# Battey_Voltage.net
KiCad netlist of a schematic drawn in Altium Designer
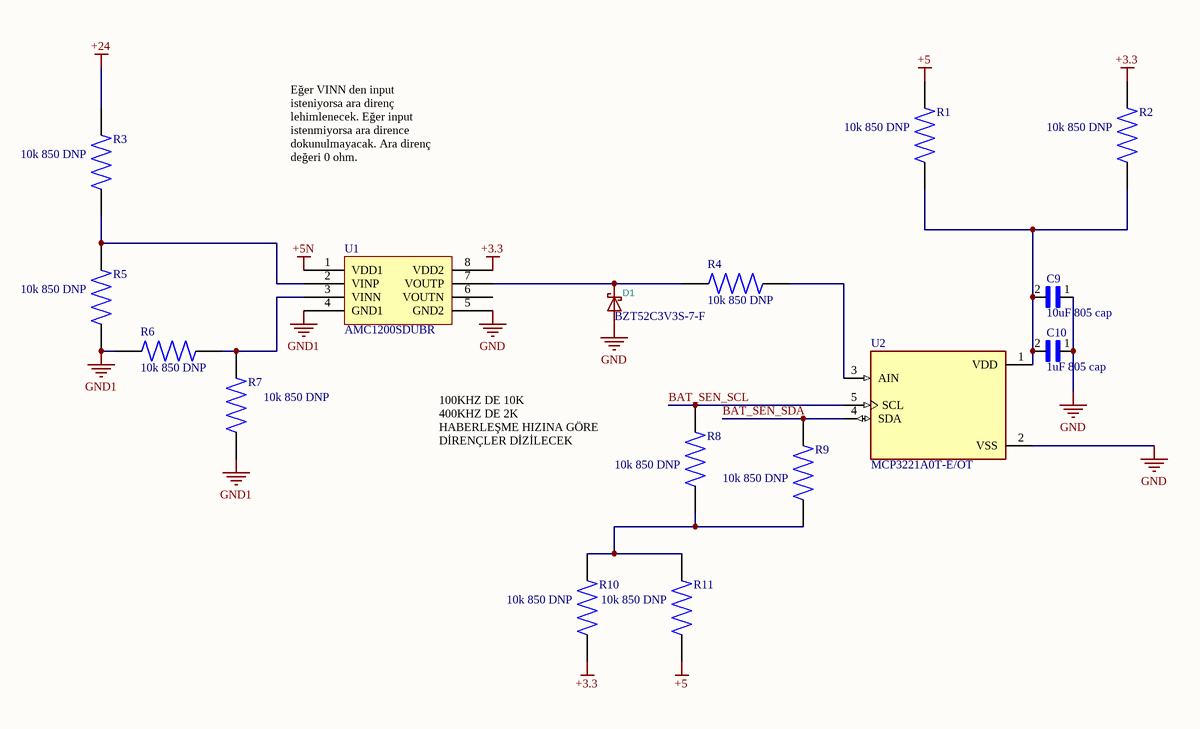
[diagram p0: Battey_Voltage.SchDoc]

(export (version "E")
  (design (tool "Eeschema 10.0.6"))
  (components
    (comp (ref "C9")
      (value "10uF 805 cap")
      (footprint "1uF 805 Cap")
      (libsource (lib "iee_altium") (part "1uF 805 cap"))
    )
    (comp (ref "C10")
      (value "1uF 805 cap")
      (footprint "1uF 805 Cap")
      (libsource (lib "iee_altium") (part "1uF 805 cap"))
    )
    (comp (ref "D1")
      (value "BZT52C3V3S-7-F")
      (footprint "SOD2513X120N")
      (libsource (lib "iee_altium") (part "BZT52C3V3S-7-F"))
    )
    (comp (ref "R1")
      (value "10k 850 DNP")
      (footprint "10k 850")
      (libsource (lib "iee_altium") (part "10k 850"))
    )
    (comp (ref "R2")
      (value "10k 850 DNP")
      (footprint "10k 850")
      (libsource (lib "iee_altium") (part "10k 850"))
    )
    (comp (ref "R3")
      (value "10k 850 DNP")
      (footprint "10k 850")
      (libsource (lib "iee_altium") (part "10k 850"))
    )
    (comp (ref "R4")
      (value "10k 850 DNP")
      (footprint "10k 850")
      (libsource (lib "iee_altium") (part "10k 850"))
    )
    (comp (ref "R5")
      (value "10k 850 DNP")
      (footprint "10k 850")
      (libsource (lib "iee_altium") (part "10k 850"))
    )
    (comp (ref "R6")
      (value "10k 850 DNP")
      (footprint "10k 850")
      (libsource (lib "iee_altium") (part "10k 850"))
    )
    (comp (ref "R7")
      (value "10k 850 DNP")
      (footprint "10k 850")
      (libsource (lib "iee_altium") (part "10k 850"))
    )
    (comp (ref "R8")
      (value "10k 850 DNP")
      (footprint "10k 850")
      (libsource (lib "iee_altium") (part "10k 850"))
    )
    (comp (ref "R9")
      (value "10k 850 DNP")
      (footprint "10k 850")
      (libsource (lib "iee_altium") (part "10k 850"))
    )
    (comp (ref "R10")
      (value "10k 850 DNP")
      (footprint "10k 850")
      (libsource (lib "iee_altium") (part "10k 850"))
    )
    (comp (ref "R11")
      (value "10k 850 DNP")
      (footprint "10k 850")
      (libsource (lib "iee_altium") (part "10k 850"))
    )
    (comp (ref "U1")
      (value "AMC1200SDUBR")
      (footprint "SOP254P1040X485-8N")
      (libsource (lib "iee_altium") (part "AMC1200SDUBR"))
    )
    (comp (ref "U2")
      (value "MCP3221A0T-E/OT")
      (footprint "SOT95P280X145-5N")
      (description "12-bit ADC, I2C, single channel5 SOT-23 T/R ¦ Microchip Technology Inc. MCP3221A0T-E/OT")
      (fields (field (name "MF") "Microchip Technology"))
      (libsource (lib "iee_altium") (part "MCP3221A0T-E/OT"))
    )
  )
  (nets
    (net (code "1") (name "+3.3") (class "Default")
      (node (ref "R10") (pin "2") (pinfunction "2_2") (pintype "passive"))
      (node (ref "R2") (pin "1") (pinfunction "1_1") (pintype "passive"))
      (node (ref "U1") (pin "8") (pinfunction "VDD2_8") (pintype "passive"))
    )
    (net (code "2") (name "+5") (class "Default")
      (node (ref "R1") (pin "1") (pinfunction "1_1") (pintype "passive"))
      (node (ref "R11") (pin "2") (pinfunction "2_2") (pintype "passive"))
    )
    (net (code "3") (name "+5N") (class "Default")
      (node (ref "U1") (pin "1") (pinfunction "VDD1_1") (pintype "passive"))
    )
    (net (code "4") (name "+24") (class "Default")
      (node (ref "R3") (pin "1") (pinfunction "1_1") (pintype "passive"))
    )
    (net (code "5") (name "/BAT_SEN_SCL") (class "Default")
      (node (ref "R8") (pin "2") (pinfunction "2_2") (pintype "passive"))
      (node (ref "U2") (pin "5") (pinfunction "SCL_5") (pintype "input"))
    )
    (net (code "6") (name "/BAT_SEN_SDA") (class "Default")
      (node (ref "R9") (pin "2") (pinfunction "2_2") (pintype "passive"))
      (node (ref "U2") (pin "4") (pinfunction "SDA_4") (pintype "bidirectional"))
    )
    (net (code "7") (name "GND") (class "Default")
      (node (ref "C10") (pin "1") (pinfunction "1_1") (pintype "passive"))
      (node (ref "C9") (pin "1") (pinfunction "1_1") (pintype "passive"))
      (node (ref "D1") (pin "A") (pinfunction "A_A") (pintype "passive"))
      (node (ref "U1") (pin "5") (pinfunction "GND2_5") (pintype "passive"))
      (node (ref "U2") (pin "2") (pinfunction "VSS_2") (pintype "power_in"))
    )
    (net (code "8") (name "GND1") (class "Default")
      (node (ref "R5") (pin "2") (pinfunction "2_2") (pintype "passive"))
      (node (ref "R6") (pin "2") (pinfunction "2_2") (pintype "passive"))
      (node (ref "R7") (pin "1") (pinfunction "1_1") (pintype "passive"))
      (node (ref "U1") (pin "4") (pinfunction "GND1_4") (pintype "passive"))
    )
    (net (code "9") (name "Net-(R10-Pad1)") (class "Default")
      (node (ref "R10") (pin "1") (pinfunction "1_1") (pintype "passive"))
      (node (ref "R11") (pin "1") (pinfunction "1_1") (pintype "passive"))
      (node (ref "R8") (pin "1") (pinfunction "1_1") (pintype "passive"))
      (node (ref "R9") (pin "1") (pinfunction "1_1") (pintype "passive"))
    )
    (net (code "10") (name "Net-(U1-VINN)") (class "Default")
      (node (ref "R6") (pin "1") (pinfunction "1_1") (pintype "passive"))
      (node (ref "R7") (pin "2") (pinfunction "2_2") (pintype "passive"))
      (node (ref "U1") (pin "3") (pinfunction "VINN_3") (pintype "passive"))
    )
    (net (code "11") (name "Net-(U1-VINP)") (class "Default")
      (node (ref "R3") (pin "2") (pinfunction "2_2") (pintype "passive"))
      (node (ref "R5") (pin "1") (pinfunction "1_1") (pintype "passive"))
      (node (ref "U1") (pin "2") (pinfunction "VINP_2") (pintype "passive"))
    )
    (net (code "12") (name "Net-(U1-VOUTP)") (class "Default")
      (node (ref "D1") (pin "K") (pinfunction "K_K") (pintype "passive"))
      (node (ref "R4") (pin "1") (pinfunction "1_1") (pintype "passive"))
      (node (ref "U1") (pin "7") (pinfunction "VOUTP_7") (pintype "passive"))
    )
    (net (code "13") (name "Net-(U2-AIN)") (class "Default")
      (node (ref "R4") (pin "2") (pinfunction "2_2") (pintype "passive"))
      (node (ref "U2") (pin "3") (pinfunction "AIN_3") (pintype "input"))
    )
    (net (code "14") (name "Net-(U2-VDD)") (class "Default")
      (node (ref "C10") (pin "2") (pinfunction "2_2") (pintype "passive"))
      (node (ref "C9") (pin "2") (pinfunction "2_2") (pintype "passive"))
      (node (ref "R1") (pin "2") (pinfunction "2_2") (pintype "passive"))
      (node (ref "R2") (pin "2") (pinfunction "2_2") (pintype "passive"))
      (node (ref "U2") (pin "1") (pinfunction "VDD_1") (pintype "power_in"))
    )
    (net (code "15") (name "unconnected-(U1-VOUTN-Pad6)") (class "Default")
      (node (ref "U1") (pin "6") (pinfunction "VOUTN_6") (pintype "passive"))
    )
  )
)
